# DC_Motor_Speed_Control.net
KiCad netlist of a schematic drawn in EAGLE
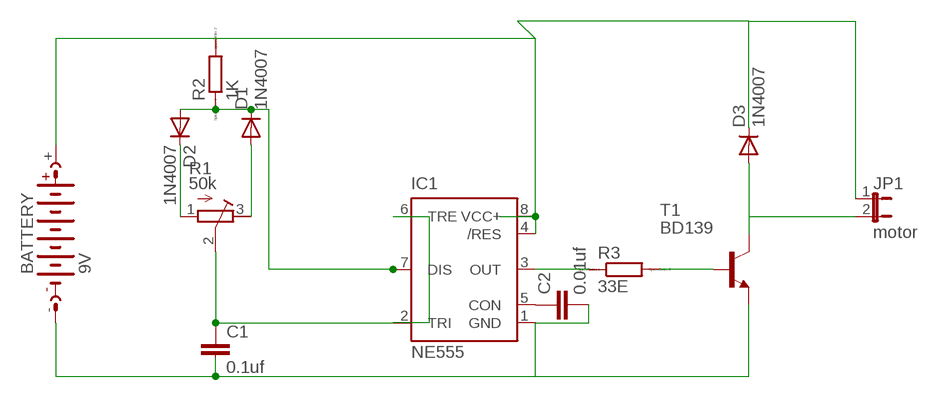
[diagram p0: schematic, sheet 1]

(export (version "E")
  (design (tool "Eeschema 10.0.6"))
  (components
    (comp (ref "BATTERY")
      (value "9V")
      (footprint "eagle-import:AB9V")
      (libsource (lib "eagle-import") (part "AB9V"))
    )
    (comp (ref "C1")
      (value "0.1uf")
      (footprint "eagle-import:C2.5-4")
      (libsource (lib "eagle-import") (part "C2.5/4"))
    )
    (comp (ref "C2")
      (value "0.01uf")
      (footprint "eagle-import:C2.5-4")
      (libsource (lib "eagle-import") (part "C2.5/4"))
    )
    (comp (ref "D1")
      (value "1N4007")
      (footprint "eagle-import:DO41-10")
      (libsource (lib "eagle-import") (part "1N4004"))
    )
    (comp (ref "D2")
      (value "1N4007")
      (footprint "eagle-import:DO41-10")
      (libsource (lib "eagle-import") (part "1N4004"))
    )
    (comp (ref "D3")
      (value "1N4007")
      (footprint "eagle-import:DO41-10")
      (libsource (lib "eagle-import") (part "1N4004"))
    )
    (comp (ref "IC1")
      (value "NE555")
      (footprint "eagle-import:DIL-08")
      (fields (field (name "MF") "Arrow Electronics") (field (name "MPN") "NE555N"))
      (libsource (lib "eagle-import") (part "NE555"))
    )
    (comp (ref "JP1")
      (value "motor")
      (footprint "eagle-import:JP1")
      (libsource (lib "eagle-import") (part "JP1E"))
    )
    (comp (ref "R1")
      (value "50k")
      (footprint "eagle-import:RTRIM64P")
      (libsource (lib "eagle-import") (part "R-TRIMM64P"))
    )
    (comp (ref "R2")
      (value "1K")
      (footprint "eagle-import:0204_7")
      (libsource (lib "eagle-import") (part "R0204/7"))
    )
    (comp (ref "R3")
      (value "33E")
      (footprint "eagle-import:0204_7")
      (libsource (lib "eagle-import") (part "R0204/7"))
    )
    (comp (ref "T1")
      (value "BD139")
      (footprint "eagle-import:TO126")
      (libsource (lib "eagle-import") (part "BD139"))
    )
  )
  (nets
    (net (code "1") (name "Net-(IC1-CON)") (class "Default")
      (node (ref "C2") (pin "1") (pinfunction "1_1") (pintype "passive"))
      (node (ref "IC1") (pin "5") (pinfunction "CON_5") (pintype "input"))
    )
    (net (code "2") (name "Net-(IC1-DIS)") (class "Default")
      (node (ref "D1") (pin "C") (pinfunction "C_C") (pintype "passive"))
      (node (ref "D2") (pin "A") (pinfunction "A_A") (pintype "passive"))
      (node (ref "IC1") (pin "7") (pinfunction "DIS_7") (pintype "input"))
      (node (ref "R2") (pin "1") (pinfunction "1_1") (pintype "passive"))
    )
    (net (code "3") (name "Net-(IC1-GND)") (class "Default")
      (node (ref "BATTERY") (pin "-") (pinfunction "-_-") (pintype "passive"))
      (node (ref "C1") (pin "2") (pinfunction "2_2") (pintype "passive"))
      (node (ref "C2") (pin "2") (pinfunction "2_2") (pintype "passive"))
      (node (ref "IC1") (pin "1") (pinfunction "GND_1") (pintype "power_in"))
      (node (ref "T1") (pin "1") (pinfunction "E_1") (pintype "passive"))
    )
    (net (code "4") (name "Net-(IC1-OUT)") (class "Default")
      (node (ref "IC1") (pin "3") (pinfunction "OUT_3") (pintype "output"))
      (node (ref "R3") (pin "1") (pinfunction "1_1") (pintype "passive"))
    )
    (net (code "5") (name "Net-(IC1-TRE)") (class "Default")
      (node (ref "C1") (pin "1") (pinfunction "1_1") (pintype "passive"))
      (node (ref "IC1") (pin "2") (pinfunction "TRI_2") (pintype "input"))
      (node (ref "IC1") (pin "6") (pinfunction "TRE_6") (pintype "input"))
      (node (ref "R1") (pin "2") (pinfunction "S_2") (pintype "passive"))
    )
    (net (code "6") (name "Net-(IC1-VCC+)") (class "Default")
      (node (ref "BATTERY") (pin "+") (pinfunction "+_+") (pintype "passive"))
      (node (ref "D3") (pin "C") (pinfunction "C_C") (pintype "passive"))
      (node (ref "IC1") (pin "4") (pinfunction "/RES_4") (pintype "input"))
      (node (ref "IC1") (pin "8") (pinfunction "VCC+_8") (pintype "power_in"))
      (node (ref "JP1") (pin "1") (pinfunction "1_1") (pintype "passive"))
      (node (ref "R2") (pin "2") (pinfunction "2_2") (pintype "passive"))
    )
    (net (code "7") (name "Net-(R1-A)") (class "Default")
      (node (ref "D1") (pin "A") (pinfunction "A_A") (pintype "passive"))
      (node (ref "R1") (pin "3") (pinfunction "A_3") (pintype "passive"))
    )
    (net (code "8") (name "Net-(R1-E)") (class "Default")
      (node (ref "D2") (pin "C") (pinfunction "C_C") (pintype "passive"))
      (node (ref "R1") (pin "1") (pinfunction "E_1") (pintype "passive"))
    )
    (net (code "9") (name "Net-(T1-B)") (class "Default")
      (node (ref "R3") (pin "2") (pinfunction "2_2") (pintype "passive"))
      (node (ref "T1") (pin "3") (pinfunction "B_3") (pintype "passive"))
    )
    (net (code "10") (name "Net-(T1-C)") (class "Default")
      (node (ref "D3") (pin "A") (pinfunction "A_A") (pintype "passive"))
      (node (ref "JP1") (pin "2") (pinfunction "2_2") (pintype "passive"))
      (node (ref "T1") (pin "2") (pinfunction "C_2") (pintype "passive"))
    )
  )
)
